# Main.net
KiCad netlist of a schematic drawn in Altium Designer
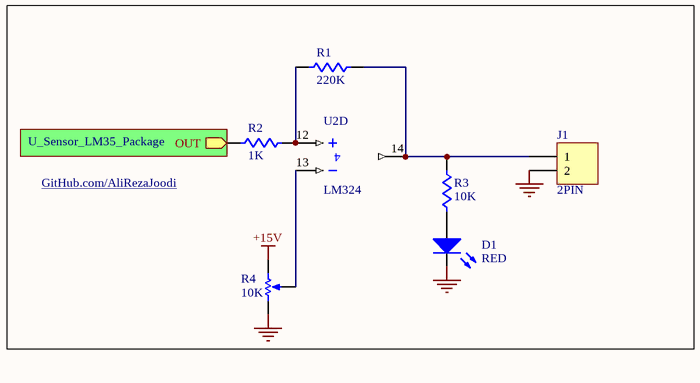
[diagram p0: Main.SchDoc]

(export (version "E")
  (design (tool "Eeschema 10.0.6"))
  (components
    (comp (ref "D1")
      (value "RED")
      (footprint "LED-5mm_Red")
      (description "Typical INFRARED GaAs LED")
      (fields (field (name "MANUFACTURER") "Generic Components") (field (name "PUBLISHER") "Altium Limited"))
      (libsource (lib "Miscellaneous Devices") (part "LED"))
    )
    (comp (ref "J1")
      (value "2PIN")
      (footprint "Fonics_2PIN_1")
      (description "Header, 2-Pin")
      (fields (field (name "MANUFACTURER") "Generic Components") (field (name "PUBLISHER") "Altium Limited"))
      (libsource (lib "Miscellaneous Connectors") (part "Header 2"))
    )
    (comp (ref "R1")
      (value "220K")
      (footprint "AXIAL-0.4")
      (description "Resistor")
      (fields (field (name "MANUFACTURER") "Generic Components") (field (name "PUBLISHER") "Altium Limited"))
      (libsource (lib "Miscellaneous Devices") (part "Res1"))
    )
    (comp (ref "R2")
      (value "1K")
      (footprint "AXIAL-0.4")
      (description "Resistor")
      (fields (field (name "MANUFACTURER") "Generic Components") (field (name "PUBLISHER") "Altium Limited"))
      (libsource (lib "Miscellaneous Devices") (part "Res1"))
    )
    (comp (ref "R3")
      (value "10K")
      (footprint "AXIAL-0.4")
      (description "Resistor")
      (fields (field (name "MANUFACTURER") "Generic Components") (field (name "PUBLISHER") "Altium Limited"))
      (libsource (lib "Miscellaneous Devices") (part "Res1"))
    )
    (comp (ref "R4")
      (value "10K")
      (footprint "VR4_")
      (description "Potentiometer")
      (fields (field (name "MANUFACTURER") "Generic Components") (field (name "PUBLISHER") "Altium Limited"))
      (libsource (lib "my Libraries") (part "RPot1"))
    )
    (comp (ref "U2")
      (value "LM324")
      (footprint "646-06")
      (description "Quad Low-Power Operational Amplifier")
      (fields (field (name "PUBLISHER") "Altium Limited"))
      (libsource (lib "my Libraries") (part "LM324"))
    )
  )
  (nets
    (net (code "1") (name "+15V") (class "Default")
      (node (ref "R4") (pin "2") (pinfunction "BOT_2") (pintype "passive"))
    )
    (net (code "2") (name "/OUT") (class "Default")
      (node (ref "R2") (pin "1") (pinfunction "1_1") (pintype "passive"))
    )
    (net (code "3") (name "GND") (class "Default")
      (node (ref "D1") (pin "2") (pinfunction "K_2") (pintype "passive"))
      (node (ref "J1") (pin "2") (pinfunction "2_2") (pintype "passive"))
      (node (ref "R4") (pin "1") (pinfunction "TOP_1") (pintype "passive"))
    )
    (net (code "4") (name "Net-(D1-A)") (class "Default")
      (node (ref "D1") (pin "1") (pinfunction "A_1") (pintype "passive"))
      (node (ref "R3") (pin "2") (pinfunction "2_2") (pintype "passive"))
    )
    (net (code "5") (name "Net-(R4-TAP)") (class "Default")
      (node (ref "R4") (pin "3") (pinfunction "TAP_3") (pintype "passive"))
      (node (ref "U2") (pin "13") (pinfunction "IN-_13") (pintype "input"))
    )
    (net (code "6") (name "Net-(U2D-IN+)") (class "Default")
      (node (ref "R1") (pin "1") (pinfunction "1_1") (pintype "passive"))
      (node (ref "R2") (pin "2") (pinfunction "2_2") (pintype "passive"))
      (node (ref "U2") (pin "12") (pinfunction "IN+_12") (pintype "input"))
    )
    (net (code "7") (name "Net-(U2D-OUT)") (class "Default")
      (node (ref "J1") (pin "1") (pinfunction "1_1") (pintype "passive"))
      (node (ref "R1") (pin "2") (pinfunction "2_2") (pintype "passive"))
      (node (ref "R3") (pin "1") (pinfunction "1_1") (pintype "passive"))
      (node (ref "U2") (pin "14") (pinfunction "OUT_14") (pintype "output"))
    )
  )
)
